# 1-Schematic_spring.net
KiCad netlist of a schematic drawn in EasyEDA
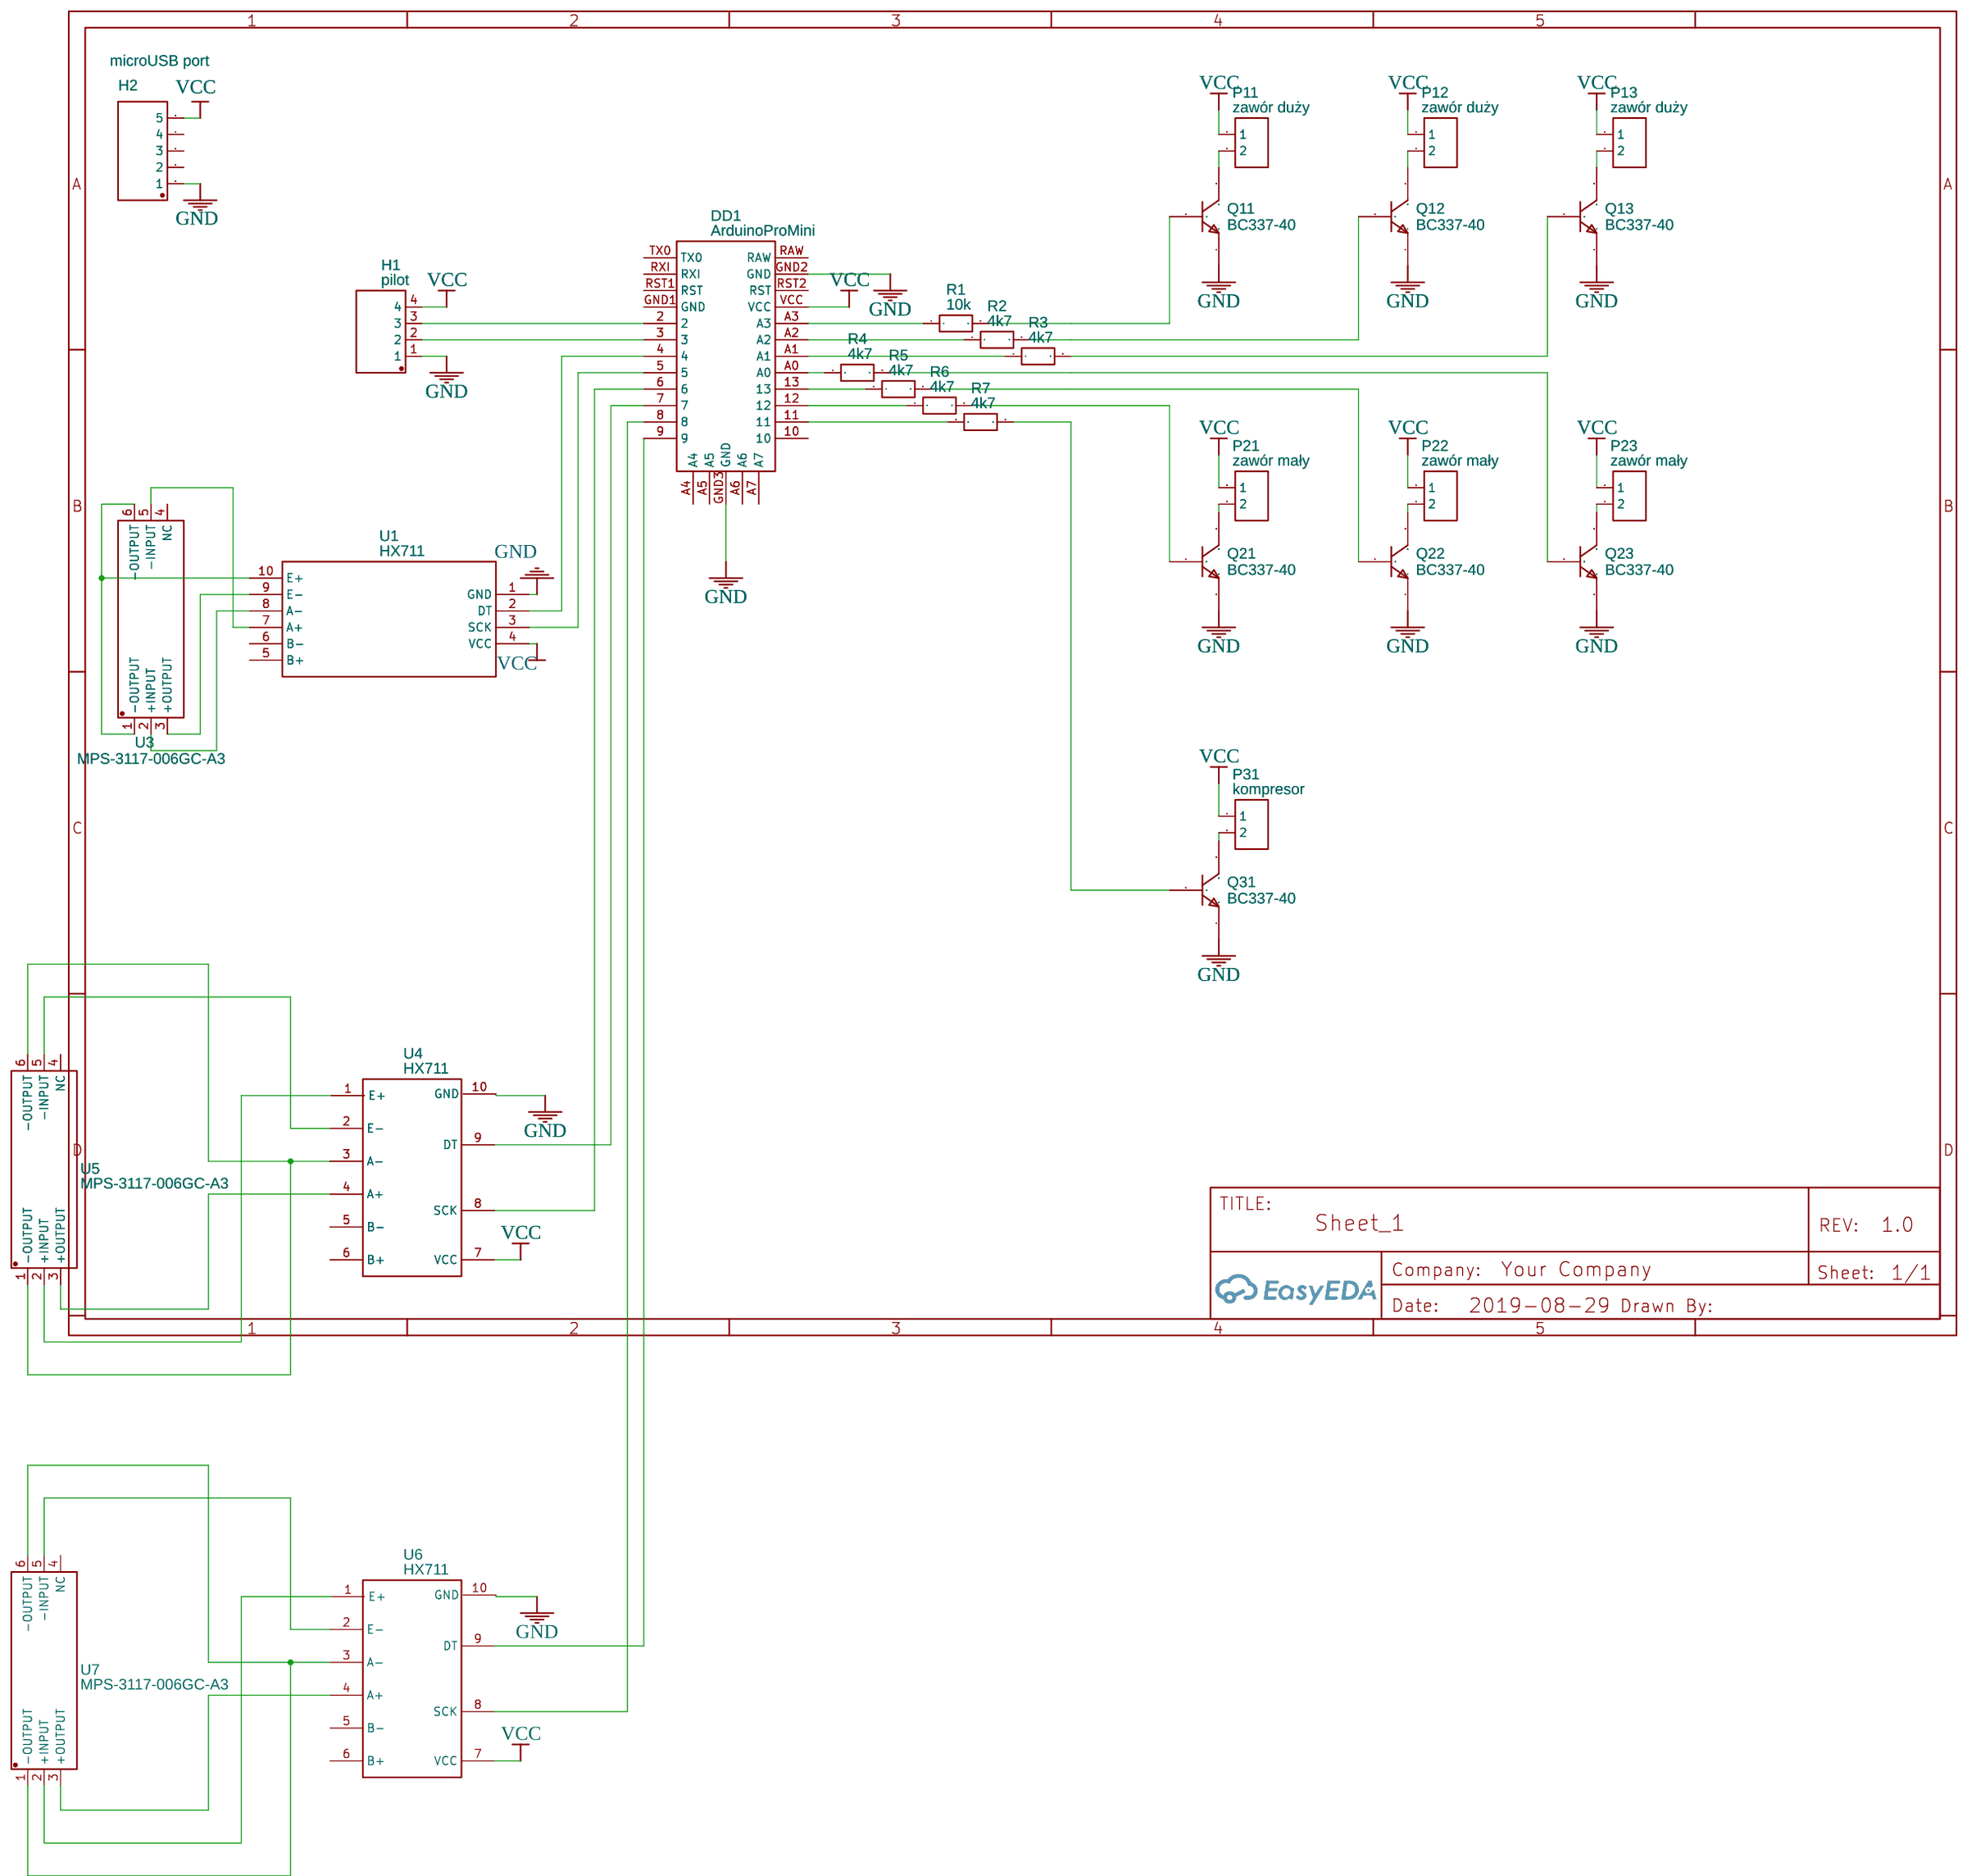
[diagram p0: schematic sheet]

(export (version "E")
  (design (tool "Eeschema 10.0.6"))
  (components
    (comp (ref "DD1") (value "ArduinoProMini") (libsource (lib "") (part "Unknown_400_140")))
    (comp (ref "H1")
      (value "pilot")
      (fields
        (field (name "BOM_Manufacturer Part") "210S-1*4P L=11.6MMGold-plated black")
        (field (name "BOM_Supplier Part") "C124378")
      )
      (libsource (lib "") (part "Unknown_195_195"))
    )
    (comp (ref "H2")
      (value "microUSB port")
      (fields
        (field (name "BOM_Manufacturer Part") "210S-1*5P L=11.6MMGold-plated black")
        (field (name "BOM_Supplier Part") "C124379")
      )
      (libsource (lib "") (part "Unknown_50_85"))
    )
    (comp (ref "P11")
      (value "zawór duży")
      (fields
        (field (name "BOM_Manufacturer Part") "2.54-1*2PFemale")
        (field (name "BOM_Supplier Part") "C49661")
      )
      (libsource (lib "") (part "Unknown_715_80"))
    )
    (comp (ref "P12")
      (value "zawór duży")
      (fields
        (field (name "BOM_Manufacturer Part") "2.54-1*2PFemale")
        (field (name "BOM_Supplier Part") "C49661")
      )
      (libsource (lib "") (part "Unknown_830_80"))
    )
    (comp (ref "P13")
      (value "zawór duży")
      (fields
        (field (name "BOM_Manufacturer Part") "2.54-1*2PFemale")
        (field (name "BOM_Supplier Part") "C49661")
      )
      (libsource (lib "") (part "Unknown_945_80"))
    )
    (comp (ref "P21")
      (value "zawór mały")
      (fields
        (field (name "BOM_Manufacturer Part") "2.54-1*2PFemale")
        (field (name "BOM_Supplier Part") "C49661")
      )
      (libsource (lib "") (part "Unknown_715_295"))
    )
    (comp (ref "P22")
      (value "zawór mały")
      (fields
        (field (name "BOM_Manufacturer Part") "2.54-1*2PFemale")
        (field (name "BOM_Supplier Part") "C49661")
      )
      (libsource (lib "") (part "Unknown_830_295"))
    )
    (comp (ref "P23")
      (value "zawór mały")
      (fields
        (field (name "BOM_Manufacturer Part") "2.54-1*2PFemale")
        (field (name "BOM_Supplier Part") "C49661")
      )
      (libsource (lib "") (part "Unknown_945_295"))
    )
    (comp (ref "P31")
      (value "kompresor")
      (fields
        (field (name "BOM_Manufacturer Part") "2.54-1*2PFemale")
        (field (name "BOM_Supplier Part") "C49661")
      )
      (libsource (lib "") (part "Unknown_715_495"))
    )
    (comp (ref "Q11") (value "BC337-40") (libsource (lib "") (part "Unknown_685_125")))
    (comp (ref "Q12") (value "BC337-40") (libsource (lib "") (part "Unknown_800_125")))
    (comp (ref "Q13") (value "BC337-40") (libsource (lib "") (part "Unknown_915_125")))
    (comp (ref "Q21") (value "BC337-40") (libsource (lib "") (part "Unknown_685_335")))
    (comp (ref "Q22") (value "BC337-40") (libsource (lib "") (part "Unknown_800_335")))
    (comp (ref "Q23") (value "BC337-40") (libsource (lib "") (part "Unknown_915_335")))
    (comp (ref "Q31") (value "BC337-40") (libsource (lib "") (part "Unknown_685_535")))
    (comp (ref "R1") (value "10k") (libsource (lib "") (part "Res_AXIAL-0.3(1/8W)_EU")))
    (comp (ref "R2") (value "4k7") (libsource (lib "") (part "Res_AXIAL-0.3(1/8W)_EU")))
    (comp (ref "R3") (value "4k7") (libsource (lib "") (part "Res_AXIAL-0.3(1/8W)_EU")))
    (comp (ref "R4") (value "4k7") (libsource (lib "") (part "Res_AXIAL-0.3(1/8W)_EU")))
    (comp (ref "R5") (value "4k7") (libsource (lib "") (part "Res_AXIAL-0.3(1/8W)_EU")))
    (comp (ref "R6") (value "4k7") (libsource (lib "") (part "Res_AXIAL-0.3(1/8W)_EU")))
    (comp (ref "R7") (value "4k7") (libsource (lib "") (part "Res_AXIAL-0.3(1/8W)_EU")))
    (comp (ref "U1") (value "HX711") (libsource (lib "") (part "Unknown_130_335")))
    (comp (ref "U3")
      (value "MPS-3117-006GC-A3")
      (fields (field (name "BOM_Supplier Part") "C242002"))
      (libsource (lib "") (part "Unknown_50_370"))
    )
    (comp (ref "U4") (value "HX711") (libsource (lib "") (part "Unknown_210_700")))
    (comp (ref "U5")
      (value "MPS-3117-006GC-A3")
      (fields (field (name "BOM_Supplier Part") "C242002"))
      (libsource (lib "") (part "Unknown_-15_705"))
    )
    (comp (ref "U6") (value "HX711") (libsource (lib "") (part "Unknown_210_1005")))
    (comp (ref "U7")
      (value "MPS-3117-006GC-A3")
      (fields (field (name "BOM_Supplier Part") "C242002"))
      (libsource (lib "") (part "Unknown_-15_1010"))
    )
  )
  (nets
    (net (code "1") (name "GND") (class "Default")
      (node (ref "DD1") (pin "GND2") (pinfunction "GND_GND2") (pintype "unspecified"))
      (node (ref "DD1") (pin "GND3") (pinfunction "GND_GND3") (pintype "unspecified"))
      (node (ref "H1") (pin "1") (pinfunction "1_1") (pintype "unspecified"))
      (node (ref "H2") (pin "1") (pinfunction "1_1") (pintype "unspecified"))
      (node (ref "Q11") (pin "1") (pinfunction "E_1") (pintype "unspecified"))
      (node (ref "Q12") (pin "1") (pinfunction "E_1") (pintype "unspecified"))
      (node (ref "Q13") (pin "1") (pinfunction "E_1") (pintype "unspecified"))
      (node (ref "Q21") (pin "1") (pinfunction "E_1") (pintype "unspecified"))
      (node (ref "Q22") (pin "1") (pinfunction "E_1") (pintype "unspecified"))
      (node (ref "Q23") (pin "1") (pinfunction "E_1") (pintype "unspecified"))
      (node (ref "Q31") (pin "1") (pinfunction "E_1") (pintype "unspecified"))
      (node (ref "U1") (pin "1") (pinfunction "GND_1") (pintype "unspecified"))
      (node (ref "U4") (pin "10") (pinfunction "GND_10") (pintype "unspecified"))
      (node (ref "U6") (pin "10") (pinfunction "GND_10") (pintype "unspecified"))
    )
    (net (code "2") (name "Net-(DD1-Pad2)") (class "Default")
      (node (ref "DD1") (pin "2") (pinfunction "2_2") (pintype "unspecified"))
      (node (ref "H1") (pin "3") (pinfunction "3_3") (pintype "unspecified"))
    )
    (net (code "3") (name "Net-(DD1-Pad3)") (class "Default")
      (node (ref "DD1") (pin "3") (pinfunction "3_3") (pintype "unspecified"))
      (node (ref "H1") (pin "2") (pinfunction "2_2") (pintype "unspecified"))
    )
    (net (code "4") (name "Net-(DD1-Pad11)") (class "Default")
      (node (ref "DD1") (pin "11") (pinfunction "11_11") (pintype "unspecified"))
      (node (ref "R7") (pin "1") (pinfunction "1_1") (pintype "unspecified"))
    )
    (net (code "5") (name "Net-(DD1-Pad12)") (class "Default")
      (node (ref "DD1") (pin "12") (pinfunction "12_12") (pintype "unspecified"))
      (node (ref "R6") (pin "1") (pinfunction "1_1") (pintype "unspecified"))
    )
    (net (code "6") (name "Net-(DD1-Pad13)") (class "Default")
      (node (ref "DD1") (pin "13") (pinfunction "13_13") (pintype "unspecified"))
      (node (ref "R5") (pin "1") (pinfunction "1_1") (pintype "unspecified"))
    )
    (net (code "7") (name "Net-(DD1-PadA0)") (class "Default")
      (node (ref "DD1") (pin "A0") (pinfunction "A0_A0") (pintype "unspecified"))
      (node (ref "R4") (pin "1") (pinfunction "1_1") (pintype "unspecified"))
    )
    (net (code "8") (name "Net-(DD1-PadA1)") (class "Default")
      (node (ref "DD1") (pin "A1") (pinfunction "A1_A1") (pintype "unspecified"))
      (node (ref "R3") (pin "1") (pinfunction "1_1") (pintype "unspecified"))
    )
    (net (code "9") (name "Net-(DD1-PadA2)") (class "Default")
      (node (ref "DD1") (pin "A2") (pinfunction "A2_A2") (pintype "unspecified"))
      (node (ref "R2") (pin "1") (pinfunction "1_1") (pintype "unspecified"))
    )
    (net (code "10") (name "Net-(DD1-PadA3)") (class "Default")
      (node (ref "DD1") (pin "A3") (pinfunction "A3_A3") (pintype "unspecified"))
      (node (ref "R1") (pin "1") (pinfunction "1_1") (pintype "unspecified"))
    )
    (net (code "11") (name "Net-(Q11-B)") (class "Default")
      (node (ref "Q11") (pin "2") (pinfunction "B_2") (pintype "unspecified"))
      (node (ref "R1") (pin "2") (pinfunction "2_2") (pintype "unspecified"))
    )
    (net (code "12") (name "Net-(Q11-C)") (class "Default")
      (node (ref "P11") (pin "2") (pinfunction "2_2") (pintype "input"))
      (node (ref "Q11") (pin "3") (pinfunction "C_3") (pintype "unspecified"))
    )
    (net (code "13") (name "Net-(Q12-B)") (class "Default")
      (node (ref "Q12") (pin "2") (pinfunction "B_2") (pintype "unspecified"))
      (node (ref "R2") (pin "2") (pinfunction "2_2") (pintype "unspecified"))
    )
    (net (code "14") (name "Net-(Q12-C)") (class "Default")
      (node (ref "P12") (pin "2") (pinfunction "2_2") (pintype "input"))
      (node (ref "Q12") (pin "3") (pinfunction "C_3") (pintype "unspecified"))
    )
    (net (code "15") (name "Net-(Q13-B)") (class "Default")
      (node (ref "Q13") (pin "2") (pinfunction "B_2") (pintype "unspecified"))
      (node (ref "R3") (pin "2") (pinfunction "2_2") (pintype "unspecified"))
    )
    (net (code "16") (name "Net-(Q13-C)") (class "Default")
      (node (ref "P13") (pin "2") (pinfunction "2_2") (pintype "input"))
      (node (ref "Q13") (pin "3") (pinfunction "C_3") (pintype "unspecified"))
    )
    (net (code "17") (name "Net-(Q21-B)") (class "Default")
      (node (ref "Q21") (pin "2") (pinfunction "B_2") (pintype "unspecified"))
      (node (ref "R6") (pin "2") (pinfunction "2_2") (pintype "unspecified"))
    )
    (net (code "18") (name "Net-(Q21-C)") (class "Default")
      (node (ref "P21") (pin "2") (pinfunction "2_2") (pintype "input"))
      (node (ref "Q21") (pin "3") (pinfunction "C_3") (pintype "unspecified"))
    )
    (net (code "19") (name "Net-(Q22-B)") (class "Default")
      (node (ref "Q22") (pin "2") (pinfunction "B_2") (pintype "unspecified"))
      (node (ref "R5") (pin "2") (pinfunction "2_2") (pintype "unspecified"))
    )
    (net (code "20") (name "Net-(Q22-C)") (class "Default")
      (node (ref "P22") (pin "2") (pinfunction "2_2") (pintype "input"))
      (node (ref "Q22") (pin "3") (pinfunction "C_3") (pintype "unspecified"))
    )
    (net (code "21") (name "Net-(Q23-B)") (class "Default")
      (node (ref "Q23") (pin "2") (pinfunction "B_2") (pintype "unspecified"))
      (node (ref "R4") (pin "2") (pinfunction "2_2") (pintype "unspecified"))
    )
    (net (code "22") (name "Net-(Q23-C)") (class "Default")
      (node (ref "P23") (pin "2") (pinfunction "2_2") (pintype "input"))
      (node (ref "Q23") (pin "3") (pinfunction "C_3") (pintype "unspecified"))
    )
    (net (code "23") (name "Net-(Q31-B)") (class "Default")
      (node (ref "Q31") (pin "2") (pinfunction "B_2") (pintype "unspecified"))
      (node (ref "R7") (pin "2") (pinfunction "2_2") (pintype "unspecified"))
    )
    (net (code "24") (name "Net-(Q31-C)") (class "Default")
      (node (ref "P31") (pin "2") (pinfunction "2_2") (pintype "input"))
      (node (ref "Q31") (pin "3") (pinfunction "C_3") (pintype "unspecified"))
    )
    (net (code "25") (name "Net-(U1-A+)") (class "Default")
      (node (ref "U1") (pin "7") (pinfunction "A+_7") (pintype "unspecified"))
      (node (ref "U3") (pin "5") (pinfunction "-INPUT_5") (pintype "unspecified"))
    )
    (net (code "26") (name "Net-(U1-A-)") (class "Default")
      (node (ref "U1") (pin "8") (pinfunction "A-_8") (pintype "unspecified"))
      (node (ref "U3") (pin "2") (pinfunction "+INPUT_2") (pintype "unspecified"))
    )
    (net (code "27") (name "Net-(U1-DT)") (class "Default")
      (node (ref "DD1") (pin "4") (pinfunction "4_4") (pintype "unspecified"))
      (node (ref "U1") (pin "2") (pinfunction "DT_2") (pintype "unspecified"))
    )
    (net (code "28") (name "Net-(U1-E+)") (class "Default")
      (node (ref "U1") (pin "10") (pinfunction "E+_10") (pintype "unspecified"))
      (node (ref "U3") (pin "1") (pinfunction "-OUTPUT_1") (pintype "unspecified"))
      (node (ref "U3") (pin "6") (pinfunction "-OUTPUT_6") (pintype "unspecified"))
    )
    (net (code "29") (name "Net-(U1-E-)") (class "Default")
      (node (ref "U1") (pin "9") (pinfunction "E-_9") (pintype "unspecified"))
      (node (ref "U3") (pin "3") (pinfunction "+OUTPUT_3") (pintype "unspecified"))
    )
    (net (code "30") (name "Net-(U1-SCK)") (class "Default")
      (node (ref "DD1") (pin "5") (pinfunction "5_5") (pintype "unspecified"))
      (node (ref "U1") (pin "3") (pinfunction "SCK_3") (pintype "unspecified"))
    )
    (net (code "31") (name "Net-(U4-A+)") (class "Default")
      (node (ref "U4") (pin "4") (pinfunction "A+_4") (pintype "unspecified"))
      (node (ref "U5") (pin "3") (pinfunction "+OUTPUT_3") (pintype "unspecified"))
    )
    (net (code "32") (name "Net-(U4-A-)") (class "Default")
      (node (ref "U4") (pin "3") (pinfunction "A-_3") (pintype "unspecified"))
      (node (ref "U5") (pin "1") (pinfunction "-OUTPUT_1") (pintype "unspecified"))
      (node (ref "U5") (pin "6") (pinfunction "-OUTPUT_6") (pintype "unspecified"))
    )
    (net (code "33") (name "Net-(U4-DT)") (class "Default")
      (node (ref "DD1") (pin "7") (pinfunction "7_7") (pintype "unspecified"))
      (node (ref "U4") (pin "9") (pinfunction "DT_9") (pintype "unspecified"))
    )
    (net (code "34") (name "Net-(U4-E+)") (class "Default")
      (node (ref "U4") (pin "1") (pinfunction "E+_1") (pintype "unspecified"))
      (node (ref "U5") (pin "2") (pinfunction "+INPUT_2") (pintype "unspecified"))
    )
    (net (code "35") (name "Net-(U4-E-)") (class "Default")
      (node (ref "U4") (pin "2") (pinfunction "E-_2") (pintype "unspecified"))
      (node (ref "U5") (pin "5") (pinfunction "-INPUT_5") (pintype "unspecified"))
    )
    (net (code "36") (name "Net-(U4-SCK)") (class "Default")
      (node (ref "DD1") (pin "6") (pinfunction "6_6") (pintype "unspecified"))
      (node (ref "U4") (pin "8") (pinfunction "SCK_8") (pintype "unspecified"))
    )
    (net (code "37") (name "Net-(U6-A+)") (class "Default")
      (node (ref "U6") (pin "4") (pinfunction "A+_4") (pintype "unspecified"))
      (node (ref "U7") (pin "3") (pinfunction "+OUTPUT_3") (pintype "unspecified"))
    )
    (net (code "38") (name "Net-(U6-A-)") (class "Default")
      (node (ref "U6") (pin "3") (pinfunction "A-_3") (pintype "unspecified"))
      (node (ref "U7") (pin "1") (pinfunction "-OUTPUT_1") (pintype "unspecified"))
      (node (ref "U7") (pin "6") (pinfunction "-OUTPUT_6") (pintype "unspecified"))
    )
    (net (code "39") (name "Net-(U6-DT)") (class "Default")
      (node (ref "DD1") (pin "9") (pinfunction "9_9") (pintype "unspecified"))
      (node (ref "U6") (pin "9") (pinfunction "DT_9") (pintype "unspecified"))
    )
    (net (code "40") (name "Net-(U6-E+)") (class "Default")
      (node (ref "U6") (pin "1") (pinfunction "E+_1") (pintype "unspecified"))
      (node (ref "U7") (pin "2") (pinfunction "+INPUT_2") (pintype "unspecified"))
    )
    (net (code "41") (name "Net-(U6-E-)") (class "Default")
      (node (ref "U6") (pin "2") (pinfunction "E-_2") (pintype "unspecified"))
      (node (ref "U7") (pin "5") (pinfunction "-INPUT_5") (pintype "unspecified"))
    )
    (net (code "42") (name "Net-(U6-SCK)") (class "Default")
      (node (ref "DD1") (pin "8") (pinfunction "8_8") (pintype "unspecified"))
      (node (ref "U6") (pin "8") (pinfunction "SCK_8") (pintype "unspecified"))
    )
    (net (code "43") (name "VCC") (class "Default")
      (node (ref "DD1") (pin "VCC") (pinfunction "VCC_VCC") (pintype "unspecified"))
      (node (ref "H1") (pin "4") (pinfunction "4_4") (pintype "unspecified"))
      (node (ref "H2") (pin "5") (pinfunction "5_5") (pintype "unspecified"))
      (node (ref "P11") (pin "1") (pinfunction "1_1") (pintype "input"))
      (node (ref "P12") (pin "1") (pinfunction "1_1") (pintype "input"))
      (node (ref "P13") (pin "1") (pinfunction "1_1") (pintype "input"))
      (node (ref "P21") (pin "1") (pinfunction "1_1") (pintype "input"))
      (node (ref "P22") (pin "1") (pinfunction "1_1") (pintype "input"))
      (node (ref "P23") (pin "1") (pinfunction "1_1") (pintype "input"))
      (node (ref "P31") (pin "1") (pinfunction "1_1") (pintype "input"))
      (node (ref "U1") (pin "4") (pinfunction "VCC_4") (pintype "unspecified"))
      (node (ref "U4") (pin "7") (pinfunction "VCC_7") (pintype "unspecified"))
      (node (ref "U6") (pin "7") (pinfunction "VCC_7") (pintype "unspecified"))
    )
    (net (code "44") (name "unconnected-(DD1-GND-PadGND1)") (class "Default")
      (node (ref "DD1") (pin "GND1") (pinfunction "GND_GND1") (pintype "unspecified"))
    )
    (net (code "45") (name "unconnected-(DD1-Pad10)") (class "Default")
      (node (ref "DD1") (pin "10") (pinfunction "10_10") (pintype "unspecified"))
    )
    (net (code "46") (name "unconnected-(DD1-PadA4)") (class "Default")
      (node (ref "DD1") (pin "A4") (pinfunction "A4_A4") (pintype "unspecified"))
    )
    (net (code "47") (name "unconnected-(DD1-PadA5)") (class "Default")
      (node (ref "DD1") (pin "A5") (pinfunction "A5_A5") (pintype "unspecified"))
    )
    (net (code "48") (name "unconnected-(DD1-PadA6)") (class "Default")
      (node (ref "DD1") (pin "A6") (pinfunction "A6_A6") (pintype "unspecified"))
    )
    (net (code "49") (name "unconnected-(DD1-PadA7)") (class "Default")
      (node (ref "DD1") (pin "A7") (pinfunction "A7_A7") (pintype "unspecified"))
    )
    (net (code "50") (name "unconnected-(DD1-PadRAW)") (class "Default")
      (node (ref "DD1") (pin "RAW") (pinfunction "RAW_RAW") (pintype "unspecified"))
    )
    (net (code "51") (name "unconnected-(DD1-PadRXI)") (class "Default")
      (node (ref "DD1") (pin "RXI") (pinfunction "RXI_RXI") (pintype "unspecified"))
    )
    (net (code "52") (name "unconnected-(DD1-PadTX0)") (class "Default")
      (node (ref "DD1") (pin "TX0") (pinfunction "TX0_TX0") (pintype "unspecified"))
    )
    (net (code "53") (name "unconnected-(DD1-RST-PadRST1)") (class "Default")
      (node (ref "DD1") (pin "RST1") (pinfunction "RST_RST1") (pintype "unspecified"))
    )
    (net (code "54") (name "unconnected-(DD1-RST-PadRST2)") (class "Default")
      (node (ref "DD1") (pin "RST2") (pinfunction "RST_RST2") (pintype "unspecified"))
    )
    (net (code "55") (name "unconnected-(H2-Pad2)") (class "Default")
      (node (ref "H2") (pin "2") (pinfunction "2_2") (pintype "unspecified"))
    )
    (net (code "56") (name "unconnected-(H2-Pad3)") (class "Default")
      (node (ref "H2") (pin "3") (pinfunction "3_3") (pintype "unspecified"))
    )
    (net (code "57") (name "unconnected-(H2-Pad4)") (class "Default")
      (node (ref "H2") (pin "4") (pinfunction "4_4") (pintype "unspecified"))
    )
    (net (code "58") (name "unconnected-(U1-B+-Pad5)") (class "Default")
      (node (ref "U1") (pin "5") (pinfunction "B+_5") (pintype "unspecified"))
    )
    (net (code "59") (name "unconnected-(U1-B--Pad6)") (class "Default")
      (node (ref "U1") (pin "6") (pinfunction "B-_6") (pintype "unspecified"))
    )
    (net (code "60") (name "unconnected-(U3-NC-Pad4)") (class "Default")
      (node (ref "U3") (pin "4") (pinfunction "NC_4") (pintype "unspecified"))
    )
    (net (code "61") (name "unconnected-(U4-B+-Pad6)") (class "Default")
      (node (ref "U4") (pin "6") (pinfunction "B+_6") (pintype "unspecified"))
    )
    (net (code "62") (name "unconnected-(U4-B--Pad5)") (class "Default")
      (node (ref "U4") (pin "5") (pinfunction "B-_5") (pintype "unspecified"))
    )
    (net (code "63") (name "unconnected-(U5-NC-Pad4)") (class "Default")
      (node (ref "U5") (pin "4") (pinfunction "NC_4") (pintype "unspecified"))
    )
    (net (code "64") (name "unconnected-(U6-B+-Pad6)") (class "Default")
      (node (ref "U6") (pin "6") (pinfunction "B+_6") (pintype "unspecified"))
    )
    (net (code "65") (name "unconnected-(U6-B--Pad5)") (class "Default")
      (node (ref "U6") (pin "5") (pinfunction "B-_5") (pintype "unspecified"))
    )
    (net (code "66") (name "unconnected-(U7-NC-Pad4)") (class "Default")
      (node (ref "U7") (pin "4") (pinfunction "NC_4") (pintype "unspecified"))
    )
  )
)
